# 3PDT.net
KiCad netlist of a schematic drawn in EAGLE
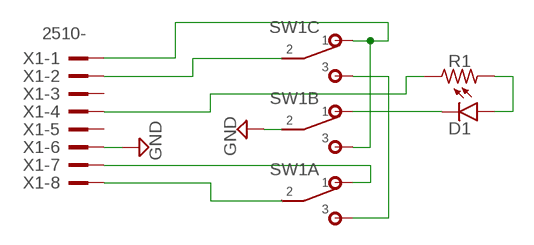
[diagram p0: schematic, sheet 1]

(export (version "E")
  (design (tool "Eeschema 10.0.6"))
  (components
    (comp (ref "D1")
      (value "LED")
      (footprint "eagle-import:3MM_D")
      (libsource (lib "eagle-import") (part "LED"))
    )
    (comp (ref "R1")
      (value "R_.3B")
      (footprint "eagle-import:R0207_3")
      (libsource (lib "eagle-import") (part "R_.3B"))
    )
    (comp (ref "SW1")
      (value "3PDT")
      (footprint "eagle-import:3PDT")
      (libsource (lib "eagle-import") (part "3PDT"))
    )
    (comp (ref "X1")
      (value "2510-")
      (footprint "eagle-import:PAK100_2500-10")
      (fields (field (name "MF") "3M") (field (name "MPN") "2510-6002UB"))
      (libsource (lib "eagle-import") (part "2510-"))
    )
  )
  (nets
    (net (code "1") (name "GND") (class "Default")
      (node (ref "SW1") (pin "B2") (pinfunction "2_B2") (pintype "passive"))
      (node (ref "X1") (pin "6") (pinfunction "KL_6") (pintype "passive"))
    )
    (net (code "2") (name "Net-(D1-A)") (class "Default")
      (node (ref "D1") (pin "ANODE") (pinfunction "A_ANODE") (pintype "passive"))
      (node (ref "R1") (pin "2") (pinfunction "2_2") (pintype "passive"))
    )
    (net (code "3") (name "Net-(D1-C)") (class "Default")
      (node (ref "D1") (pin "P$1") (pinfunction "C_P$1") (pintype "passive"))
      (node (ref "SW1") (pin "B1") (pinfunction "1_B1") (pintype "passive"))
    )
    (net (code "4") (name "Net-(SW1A-1)") (class "Default")
      (node (ref "SW1") (pin "A1") (pinfunction "1_A1") (pintype "passive"))
      (node (ref "X1") (pin "7") (pinfunction "KL_7") (pintype "passive"))
    )
    (net (code "5") (name "Net-(SW1A-2)") (class "Default")
      (node (ref "SW1") (pin "A2") (pinfunction "2_A2") (pintype "passive"))
      (node (ref "X1") (pin "8") (pinfunction "KL_8") (pintype "passive"))
    )
    (net (code "6") (name "Net-(SW1A-3)") (class "Default")
      (node (ref "SW1") (pin "A3") (pinfunction "3_A3") (pintype "passive"))
      (node (ref "SW1") (pin "C3") (pinfunction "3_C3") (pintype "passive"))
    )
    (net (code "7") (name "Net-(SW1B-3)") (class "Default")
      (node (ref "SW1") (pin "B3") (pinfunction "3_B3") (pintype "passive"))
      (node (ref "SW1") (pin "C1") (pinfunction "1_C1") (pintype "passive"))
      (node (ref "X1") (pin "1") (pinfunction "KL_1") (pintype "passive"))
    )
    (net (code "8") (name "Net-(SW1C-2)") (class "Default")
      (node (ref "SW1") (pin "C2") (pinfunction "2_C2") (pintype "passive"))
      (node (ref "X1") (pin "2") (pinfunction "KL_2") (pintype "passive"))
    )
    (net (code "9") (name "Net-(X1D-KL)") (class "Default")
      (node (ref "R1") (pin "1") (pinfunction "1_1") (pintype "passive"))
      (node (ref "X1") (pin "4") (pinfunction "KL_4") (pintype "passive"))
    )
    (net (code "10") (name "unconnected-(X1C-KL-Pad3)") (class "Default")
      (node (ref "X1") (pin "3") (pinfunction "KL_3") (pintype "passive"))
    )
    (net (code "11") (name "unconnected-(X1E-KL-Pad5)") (class "Default")
      (node (ref "X1") (pin "5") (pinfunction "KL_5") (pintype "passive"))
    )
  )
)
